# SCH_Left-hand_2023-03-17.net
KiCad netlist of a schematic drawn in EasyEDA
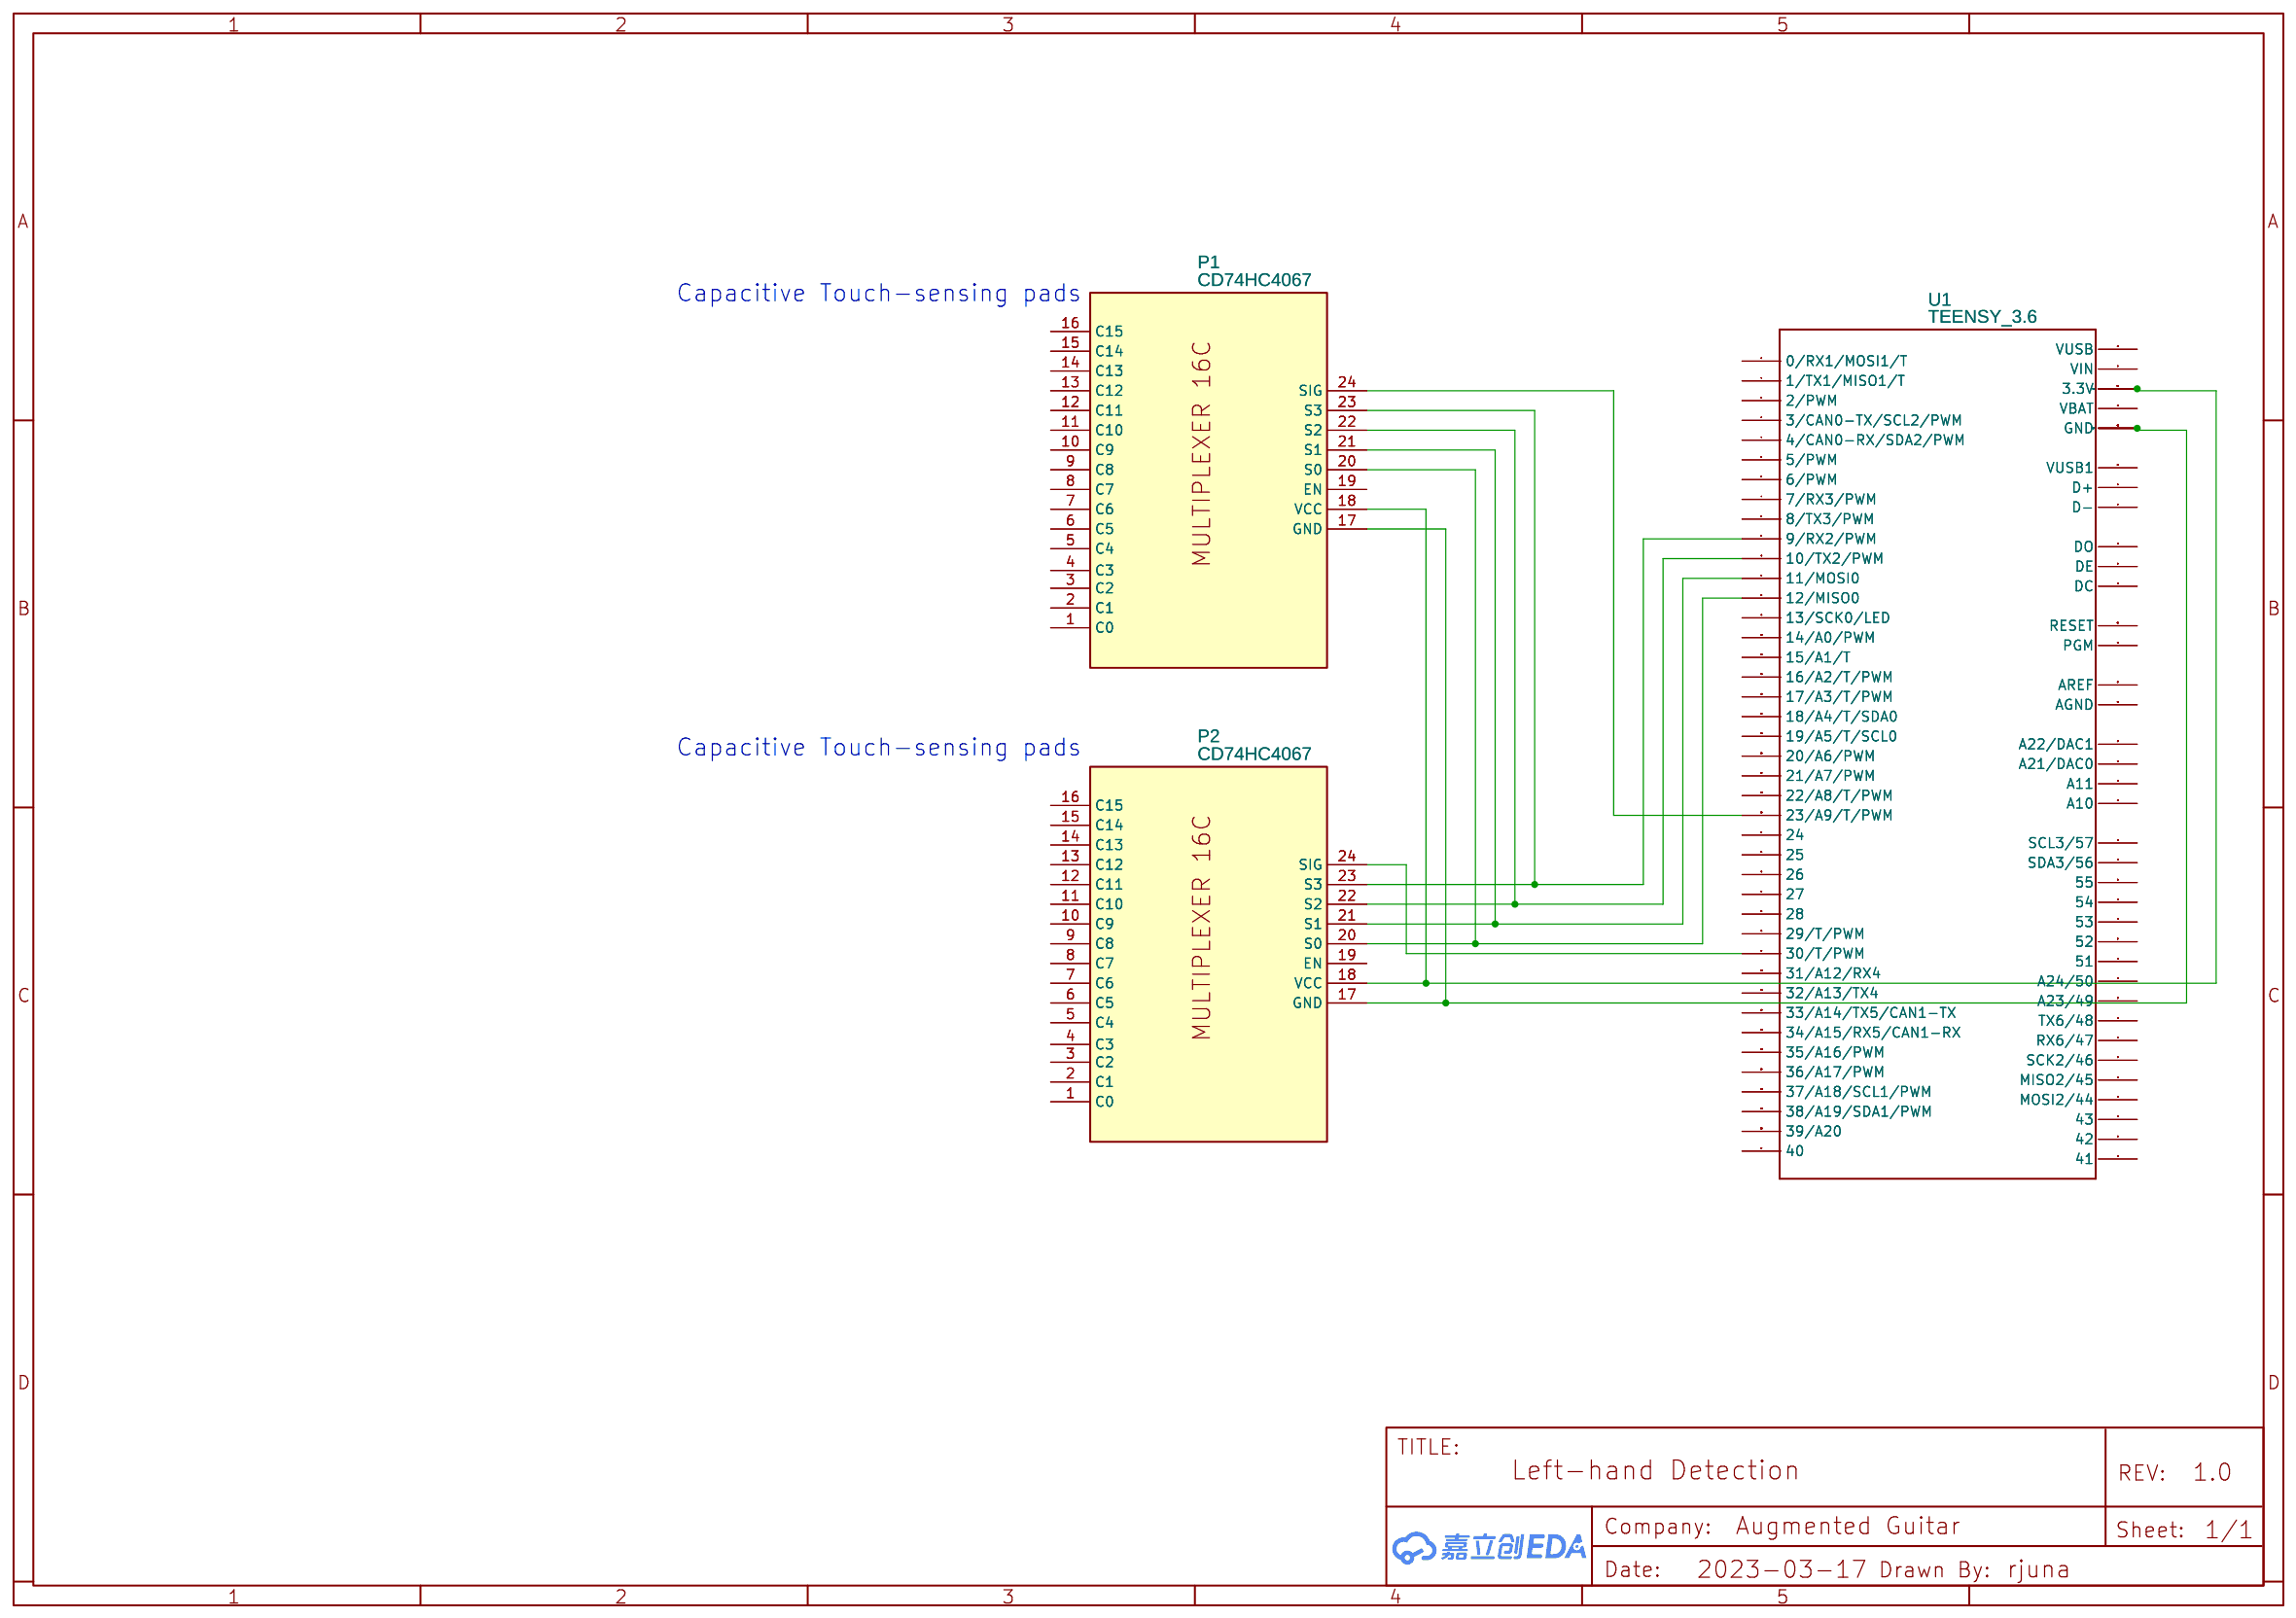
[diagram p0: schematic sheet]

(export (version "E")
  (design (tool "Eeschema 10.0.6"))
  (components
    (comp (ref "P1") (value "CD74HC4067") (libsource (lib "") (part "CD74HC4067")))
    (comp (ref "P2") (value "CD74HC4067") (libsource (lib "") (part "CD74HC4067")))
    (comp (ref "U1") (value "TEENSY_3.6") (libsource (lib "") (part "TEENSY_3.6")))
  )
  (nets
    (net (code "1") (name "Net-(P1-GND)") (class "Default")
      (node (ref "P1") (pin "17") (pinfunction "GND_17") (pintype "unspecified"))
      (node (ref "P2") (pin "17") (pinfunction "GND_17") (pintype "unspecified"))
      (node (ref "U1") (pin "GND") (pinfunction "GND_GND") (pintype "bidirectional"))
      (node (ref "U1") (pin "GND1") (pinfunction "GND_GND1") (pintype "bidirectional"))
      (node (ref "U1") (pin "GND2") (pinfunction "GND_GND2") (pintype "bidirectional"))
      (node (ref "U1") (pin "GND3") (pinfunction "GND_GND3") (pintype "bidirectional"))
      (node (ref "U1") (pin "GND4") (pinfunction "GND_GND4") (pintype "bidirectional"))
      (node (ref "U1") (pin "GND5") (pinfunction "GND_GND5") (pintype "bidirectional"))
      (node (ref "U1") (pin "GND6") (pinfunction "GND_GND6") (pintype "bidirectional"))
    )
    (net (code "2") (name "Net-(P1-S0)") (class "Default")
      (node (ref "P1") (pin "20") (pinfunction "S0_20") (pintype "unspecified"))
      (node (ref "P2") (pin "20") (pinfunction "S0_20") (pintype "unspecified"))
      (node (ref "U1") (pin "12") (pinfunction "12/MISO0_12") (pintype "bidirectional"))
    )
    (net (code "3") (name "Net-(P1-S1)") (class "Default")
      (node (ref "P1") (pin "21") (pinfunction "S1_21") (pintype "unspecified"))
      (node (ref "P2") (pin "21") (pinfunction "S1_21") (pintype "unspecified"))
      (node (ref "U1") (pin "11") (pinfunction "11/MOSI0_11") (pintype "bidirectional"))
    )
    (net (code "4") (name "Net-(P1-S2)") (class "Default")
      (node (ref "P1") (pin "22") (pinfunction "S2_22") (pintype "unspecified"))
      (node (ref "P2") (pin "22") (pinfunction "S2_22") (pintype "unspecified"))
      (node (ref "U1") (pin "10") (pinfunction "10/TX2/PWM_10") (pintype "bidirectional"))
    )
    (net (code "5") (name "Net-(P1-S3)") (class "Default")
      (node (ref "P1") (pin "23") (pinfunction "S3_23") (pintype "unspecified"))
      (node (ref "P2") (pin "23") (pinfunction "S3_23") (pintype "unspecified"))
      (node (ref "U1") (pin "9") (pinfunction "9/RX2/PWM_9") (pintype "bidirectional"))
    )
    (net (code "6") (name "Net-(P1-SIG)") (class "Default")
      (node (ref "P1") (pin "24") (pinfunction "SIG_24") (pintype "unspecified"))
      (node (ref "U1") (pin "23/A9") (pinfunction "23/A9/T/PWM_23/A9") (pintype "bidirectional"))
    )
    (net (code "7") (name "Net-(P1-VCC)") (class "Default")
      (node (ref "P1") (pin "18") (pinfunction "VCC_18") (pintype "unspecified"))
      (node (ref "P2") (pin "18") (pinfunction "VCC_18") (pintype "unspecified"))
      (node (ref "U1") (pin "3.3V") (pinfunction "3.3V_3.3V") (pintype "bidirectional"))
      (node (ref "U1") (pin "3.3V2") (pinfunction "3.3V_3.3V2") (pintype "bidirectional"))
      (node (ref "U1") (pin "3.3V3") (pinfunction "3.3V_3.3V3") (pintype "bidirectional"))
      (node (ref "U1") (pin "3.3V4") (pinfunction "3.3V_3.3V4") (pintype "bidirectional"))
    )
    (net (code "8") (name "Net-(P2-SIG)") (class "Default")
      (node (ref "P2") (pin "24") (pinfunction "SIG_24") (pintype "unspecified"))
      (node (ref "U1") (pin "30") (pinfunction "30/T/PWM_30") (pintype "bidirectional"))
    )
    (net (code "9") (name "unconnected-(P1-C0-Pad1)") (class "Default")
      (node (ref "P1") (pin "1") (pinfunction "C0_1") (pintype "unspecified"))
    )
    (net (code "10") (name "unconnected-(P1-C1-Pad2)") (class "Default")
      (node (ref "P1") (pin "2") (pinfunction "C1_2") (pintype "unspecified"))
    )
    (net (code "11") (name "unconnected-(P1-C2-Pad3)") (class "Default")
      (node (ref "P1") (pin "3") (pinfunction "C2_3") (pintype "unspecified"))
    )
    (net (code "12") (name "unconnected-(P1-C3-Pad4)") (class "Default")
      (node (ref "P1") (pin "4") (pinfunction "C3_4") (pintype "unspecified"))
    )
    (net (code "13") (name "unconnected-(P1-C4-Pad5)") (class "Default")
      (node (ref "P1") (pin "5") (pinfunction "C4_5") (pintype "unspecified"))
    )
    (net (code "14") (name "unconnected-(P1-C5-Pad6)") (class "Default")
      (node (ref "P1") (pin "6") (pinfunction "C5_6") (pintype "unspecified"))
    )
    (net (code "15") (name "unconnected-(P1-C6-Pad7)") (class "Default")
      (node (ref "P1") (pin "7") (pinfunction "C6_7") (pintype "unspecified"))
    )
    (net (code "16") (name "unconnected-(P1-C7-Pad8)") (class "Default")
      (node (ref "P1") (pin "8") (pinfunction "C7_8") (pintype "unspecified"))
    )
    (net (code "17") (name "unconnected-(P1-C8-Pad9)") (class "Default")
      (node (ref "P1") (pin "9") (pinfunction "C8_9") (pintype "unspecified"))
    )
    (net (code "18") (name "unconnected-(P1-C9-Pad10)") (class "Default")
      (node (ref "P1") (pin "10") (pinfunction "C9_10") (pintype "unspecified"))
    )
    (net (code "19") (name "unconnected-(P1-C10-Pad11)") (class "Default")
      (node (ref "P1") (pin "11") (pinfunction "C10_11") (pintype "unspecified"))
    )
    (net (code "20") (name "unconnected-(P1-C11-Pad12)") (class "Default")
      (node (ref "P1") (pin "12") (pinfunction "C11_12") (pintype "unspecified"))
    )
    (net (code "21") (name "unconnected-(P1-C12-Pad13)") (class "Default")
      (node (ref "P1") (pin "13") (pinfunction "C12_13") (pintype "unspecified"))
    )
    (net (code "22") (name "unconnected-(P1-C13-Pad14)") (class "Default")
      (node (ref "P1") (pin "14") (pinfunction "C13_14") (pintype "unspecified"))
    )
    (net (code "23") (name "unconnected-(P1-C14-Pad15)") (class "Default")
      (node (ref "P1") (pin "15") (pinfunction "C14_15") (pintype "unspecified"))
    )
    (net (code "24") (name "unconnected-(P1-C15-Pad16)") (class "Default")
      (node (ref "P1") (pin "16") (pinfunction "C15_16") (pintype "unspecified"))
    )
    (net (code "25") (name "unconnected-(P1-EN-Pad19)") (class "Default")
      (node (ref "P1") (pin "19") (pinfunction "EN_19") (pintype "unspecified"))
    )
    (net (code "26") (name "unconnected-(P2-C0-Pad1)") (class "Default")
      (node (ref "P2") (pin "1") (pinfunction "C0_1") (pintype "unspecified"))
    )
    (net (code "27") (name "unconnected-(P2-C1-Pad2)") (class "Default")
      (node (ref "P2") (pin "2") (pinfunction "C1_2") (pintype "unspecified"))
    )
    (net (code "28") (name "unconnected-(P2-C2-Pad3)") (class "Default")
      (node (ref "P2") (pin "3") (pinfunction "C2_3") (pintype "unspecified"))
    )
    (net (code "29") (name "unconnected-(P2-C3-Pad4)") (class "Default")
      (node (ref "P2") (pin "4") (pinfunction "C3_4") (pintype "unspecified"))
    )
    (net (code "30") (name "unconnected-(P2-C4-Pad5)") (class "Default")
      (node (ref "P2") (pin "5") (pinfunction "C4_5") (pintype "unspecified"))
    )
    (net (code "31") (name "unconnected-(P2-C5-Pad6)") (class "Default")
      (node (ref "P2") (pin "6") (pinfunction "C5_6") (pintype "unspecified"))
    )
    (net (code "32") (name "unconnected-(P2-C6-Pad7)") (class "Default")
      (node (ref "P2") (pin "7") (pinfunction "C6_7") (pintype "unspecified"))
    )
    (net (code "33") (name "unconnected-(P2-C7-Pad8)") (class "Default")
      (node (ref "P2") (pin "8") (pinfunction "C7_8") (pintype "unspecified"))
    )
    (net (code "34") (name "unconnected-(P2-C8-Pad9)") (class "Default")
      (node (ref "P2") (pin "9") (pinfunction "C8_9") (pintype "unspecified"))
    )
    (net (code "35") (name "unconnected-(P2-C9-Pad10)") (class "Default")
      (node (ref "P2") (pin "10") (pinfunction "C9_10") (pintype "unspecified"))
    )
    (net (code "36") (name "unconnected-(P2-C10-Pad11)") (class "Default")
      (node (ref "P2") (pin "11") (pinfunction "C10_11") (pintype "unspecified"))
    )
    (net (code "37") (name "unconnected-(P2-C11-Pad12)") (class "Default")
      (node (ref "P2") (pin "12") (pinfunction "C11_12") (pintype "unspecified"))
    )
    (net (code "38") (name "unconnected-(P2-C12-Pad13)") (class "Default")
      (node (ref "P2") (pin "13") (pinfunction "C12_13") (pintype "unspecified"))
    )
    (net (code "39") (name "unconnected-(P2-C13-Pad14)") (class "Default")
      (node (ref "P2") (pin "14") (pinfunction "C13_14") (pintype "unspecified"))
    )
    (net (code "40") (name "unconnected-(P2-C14-Pad15)") (class "Default")
      (node (ref "P2") (pin "15") (pinfunction "C14_15") (pintype "unspecified"))
    )
    (net (code "41") (name "unconnected-(P2-C15-Pad16)") (class "Default")
      (node (ref "P2") (pin "16") (pinfunction "C15_16") (pintype "unspecified"))
    )
    (net (code "42") (name "unconnected-(P2-EN-Pad19)") (class "Default")
      (node (ref "P2") (pin "19") (pinfunction "EN_19") (pintype "unspecified"))
    )
    (net (code "43") (name "unconnected-(U1-0{slash}RX1{slash}MOSI1{slash}T-Pad0)") (class "Default")
      (node (ref "U1") (pin "0") (pinfunction "0/RX1/MOSI1/T_0") (pintype "bidirectional"))
    )
    (net (code "44") (name "unconnected-(U1-1{slash}TX1{slash}MISO1{slash}T-Pad1)") (class "Default")
      (node (ref "U1") (pin "1") (pinfunction "1/TX1/MISO1/T_1") (pintype "bidirectional"))
    )
    (net (code "45") (name "unconnected-(U1-2{slash}PWM-Pad2)") (class "Default")
      (node (ref "U1") (pin "2") (pinfunction "2/PWM_2") (pintype "bidirectional"))
    )
    (net (code "46") (name "unconnected-(U1-3{slash}CAN0-TX{slash}SCL2{slash}PWM-Pad3)") (class "Default")
      (node (ref "U1") (pin "3") (pinfunction "3/CAN0-TX/SCL2/PWM_3") (pintype "bidirectional"))
    )
    (net (code "47") (name "unconnected-(U1-4{slash}CAN0-RX{slash}SDA2{slash}PWM-Pad4)") (class "Default")
      (node (ref "U1") (pin "4") (pinfunction "4/CAN0-RX/SDA2/PWM_4") (pintype "bidirectional"))
    )
    (net (code "48") (name "unconnected-(U1-5{slash}PWM-Pad5)") (class "Default")
      (node (ref "U1") (pin "5") (pinfunction "5/PWM_5") (pintype "bidirectional"))
    )
    (net (code "49") (name "unconnected-(U1-6{slash}PWM-Pad6)") (class "Default")
      (node (ref "U1") (pin "6") (pinfunction "6/PWM_6") (pintype "bidirectional"))
    )
    (net (code "50") (name "unconnected-(U1-7{slash}RX3{slash}PWM-Pad7)") (class "Default")
      (node (ref "U1") (pin "7") (pinfunction "7/RX3/PWM_7") (pintype "bidirectional"))
    )
    (net (code "51") (name "unconnected-(U1-8{slash}TX3{slash}PWM-Pad8)") (class "Default")
      (node (ref "U1") (pin "8") (pinfunction "8/TX3/PWM_8") (pintype "bidirectional"))
    )
    (net (code "52") (name "unconnected-(U1-13{slash}SCK0{slash}LED-Pad13)") (class "Default")
      (node (ref "U1") (pin "13") (pinfunction "13/SCK0/LED_13") (pintype "bidirectional"))
    )
    (net (code "53") (name "unconnected-(U1-14{slash}A0{slash}PWM-Pad14{slash}A0)") (class "Default")
      (node (ref "U1") (pin "14/A0") (pinfunction "14/A0/PWM_14/A0") (pintype "bidirectional"))
    )
    (net (code "54") (name "unconnected-(U1-15{slash}A1{slash}T-Pad15{slash}A1)") (class "Default")
      (node (ref "U1") (pin "15/A1") (pinfunction "15/A1/T_15/A1") (pintype "bidirectional"))
    )
    (net (code "55") (name "unconnected-(U1-16{slash}A2{slash}T{slash}PWM-Pad16{slash}A2)") (class "Default")
      (node (ref "U1") (pin "16/A2") (pinfunction "16/A2/T/PWM_16/A2") (pintype "bidirectional"))
    )
    (net (code "56") (name "unconnected-(U1-17{slash}A3{slash}T{slash}PWM-Pad17{slash}A3)") (class "Default")
      (node (ref "U1") (pin "17/A3") (pinfunction "17/A3/T/PWM_17/A3") (pintype "bidirectional"))
    )
    (net (code "57") (name "unconnected-(U1-18{slash}A4{slash}T{slash}SDA0-Pad18{slash}A4)") (class "Default")
      (node (ref "U1") (pin "18/A4") (pinfunction "18/A4/T/SDA0_18/A4") (pintype "bidirectional"))
    )
    (net (code "58") (name "unconnected-(U1-19{slash}A5{slash}T{slash}SCL0-Pad19{slash}A5)") (class "Default")
      (node (ref "U1") (pin "19/A5") (pinfunction "19/A5/T/SCL0_19/A5") (pintype "bidirectional"))
    )
    (net (code "59") (name "unconnected-(U1-20{slash}A6{slash}PWM-Pad20{slash}A6)") (class "Default")
      (node (ref "U1") (pin "20/A6") (pinfunction "20/A6/PWM_20/A6") (pintype "bidirectional"))
    )
    (net (code "60") (name "unconnected-(U1-21{slash}A7{slash}PWM-Pad21{slash}A7)") (class "Default")
      (node (ref "U1") (pin "21/A7") (pinfunction "21/A7/PWM_21/A7") (pintype "bidirectional"))
    )
    (net (code "61") (name "unconnected-(U1-22{slash}A8{slash}T{slash}PWM-Pad22{slash}A8)") (class "Default")
      (node (ref "U1") (pin "22/A8") (pinfunction "22/A8/T/PWM_22/A8") (pintype "bidirectional"))
    )
    (net (code "62") (name "unconnected-(U1-29{slash}T{slash}PWM-Pad29)") (class "Default")
      (node (ref "U1") (pin "29") (pinfunction "29/T/PWM_29") (pintype "bidirectional"))
    )
    (net (code "63") (name "unconnected-(U1-31{slash}A12{slash}RX4-Pad31{slash}A12)") (class "Default")
      (node (ref "U1") (pin "31/A12") (pinfunction "31/A12/RX4_31/A12") (pintype "bidirectional"))
    )
    (net (code "64") (name "unconnected-(U1-32{slash}A13{slash}TX4-Pad32{slash}A13)") (class "Default")
      (node (ref "U1") (pin "32/A13") (pinfunction "32/A13/TX4_32/A13") (pintype "bidirectional"))
    )
    (net (code "65") (name "unconnected-(U1-33{slash}A14{slash}TX5{slash}CAN1-TX-Pad33{slash}A14)") (class "Default")
      (node (ref "U1") (pin "33/A14") (pinfunction "33/A14/TX5/CAN1-TX_33/A14") (pintype "bidirectional"))
    )
    (net (code "66") (name "unconnected-(U1-34{slash}A15{slash}RX5{slash}CAN1-RX-Pad34{slash}A15)") (class "Default")
      (node (ref "U1") (pin "34/A15") (pinfunction "34/A15/RX5/CAN1-RX_34/A15") (pintype "bidirectional"))
    )
    (net (code "67") (name "unconnected-(U1-35{slash}A16{slash}PWM-Pad35{slash}A16)") (class "Default")
      (node (ref "U1") (pin "35/A16") (pinfunction "35/A16/PWM_35/A16") (pintype "bidirectional"))
    )
    (net (code "68") (name "unconnected-(U1-36{slash}A17{slash}PWM-Pad36{slash}A17)") (class "Default")
      (node (ref "U1") (pin "36/A17") (pinfunction "36/A17/PWM_36/A17") (pintype "bidirectional"))
    )
    (net (code "69") (name "unconnected-(U1-37{slash}A18{slash}SCL1{slash}PWM-Pad37{slash}A18)") (class "Default")
      (node (ref "U1") (pin "37/A18") (pinfunction "37/A18/SCL1/PWM_37/A18") (pintype "bidirectional"))
    )
    (net (code "70") (name "unconnected-(U1-38{slash}A19{slash}SDA1{slash}PWM-Pad38{slash}A19)") (class "Default")
      (node (ref "U1") (pin "38/A19") (pinfunction "38/A19/SDA1/PWM_38/A19") (pintype "bidirectional"))
    )
    (net (code "71") (name "unconnected-(U1-A21{slash}DAC0-PadA21)") (class "Default")
      (node (ref "U1") (pin "A21") (pinfunction "A21/DAC0_A21") (pintype "bidirectional"))
    )
    (net (code "72") (name "unconnected-(U1-A22{slash}DAC1-PadA22)") (class "Default")
      (node (ref "U1") (pin "A22") (pinfunction "A22/DAC1_A22") (pintype "bidirectional"))
    )
    (net (code "73") (name "unconnected-(U1-A23{slash}49-Pad49)") (class "Default")
      (node (ref "U1") (pin "49") (pinfunction "A23/49_49") (pintype "bidirectional"))
    )
    (net (code "74") (name "unconnected-(U1-A24{slash}50-Pad50)") (class "Default")
      (node (ref "U1") (pin "50") (pinfunction "A24/50_50") (pintype "bidirectional"))
    )
    (net (code "75") (name "unconnected-(U1-MISO2{slash}45-Pad45)") (class "Default")
      (node (ref "U1") (pin "45") (pinfunction "MISO2/45_45") (pintype "bidirectional"))
    )
    (net (code "76") (name "unconnected-(U1-MOSI2{slash}44-Pad44)") (class "Default")
      (node (ref "U1") (pin "44") (pinfunction "MOSI2/44_44") (pintype "bidirectional"))
    )
    (net (code "77") (name "unconnected-(U1-Pad24)") (class "Default")
      (node (ref "U1") (pin "24") (pinfunction "24_24") (pintype "bidirectional"))
    )
    (net (code "78") (name "unconnected-(U1-Pad25)") (class "Default")
      (node (ref "U1") (pin "25") (pinfunction "25_25") (pintype "bidirectional"))
    )
    (net (code "79") (name "unconnected-(U1-Pad26)") (class "Default")
      (node (ref "U1") (pin "26") (pinfunction "26_26") (pintype "bidirectional"))
    )
    (net (code "80") (name "unconnected-(U1-Pad27)") (class "Default")
      (node (ref "U1") (pin "27") (pinfunction "27_27") (pintype "bidirectional"))
    )
    (net (code "81") (name "unconnected-(U1-Pad28)") (class "Default")
      (node (ref "U1") (pin "28") (pinfunction "28_28") (pintype "bidirectional"))
    )
    (net (code "82") (name "unconnected-(U1-Pad39{slash}A20)") (class "Default")
      (node (ref "U1") (pin "39/A20") (pinfunction "39/A20_39/A20") (pintype "bidirectional"))
    )
    (net (code "83") (name "unconnected-(U1-Pad40)") (class "Default")
      (node (ref "U1") (pin "40") (pinfunction "40_40") (pintype "bidirectional"))
    )
    (net (code "84") (name "unconnected-(U1-Pad41)") (class "Default")
      (node (ref "U1") (pin "41") (pinfunction "41_41") (pintype "bidirectional"))
    )
    (net (code "85") (name "unconnected-(U1-Pad42)") (class "Default")
      (node (ref "U1") (pin "42") (pinfunction "42_42") (pintype "bidirectional"))
    )
    (net (code "86") (name "unconnected-(U1-Pad43)") (class "Default")
      (node (ref "U1") (pin "43") (pinfunction "43_43") (pintype "bidirectional"))
    )
    (net (code "87") (name "unconnected-(U1-Pad51)") (class "Default")
      (node (ref "U1") (pin "51") (pinfunction "51_51") (pintype "bidirectional"))
    )
    (net (code "88") (name "unconnected-(U1-Pad52)") (class "Default")
      (node (ref "U1") (pin "52") (pinfunction "52_52") (pintype "bidirectional"))
    )
    (net (code "89") (name "unconnected-(U1-Pad53)") (class "Default")
      (node (ref "U1") (pin "53") (pinfunction "53_53") (pintype "bidirectional"))
    )
    (net (code "90") (name "unconnected-(U1-Pad54)") (class "Default")
      (node (ref "U1") (pin "54") (pinfunction "54_54") (pintype "bidirectional"))
    )
    (net (code "91") (name "unconnected-(U1-Pad55)") (class "Default")
      (node (ref "U1") (pin "55") (pinfunction "55_55") (pintype "bidirectional"))
    )
    (net (code "92") (name "unconnected-(U1-PadA10)") (class "Default")
      (node (ref "U1") (pin "A10") (pinfunction "A10_A10") (pintype "bidirectional"))
    )
    (net (code "93") (name "unconnected-(U1-PadA11)") (class "Default")
      (node (ref "U1") (pin "A11") (pinfunction "A11_A11") (pintype "bidirectional"))
    )
    (net (code "94") (name "unconnected-(U1-PadAGND)") (class "Default")
      (node (ref "U1") (pin "AGND") (pinfunction "AGND_AGND") (pintype "bidirectional"))
    )
    (net (code "95") (name "unconnected-(U1-PadAREF)") (class "Default")
      (node (ref "U1") (pin "AREF") (pinfunction "AREF_AREF") (pintype "bidirectional"))
    )
    (net (code "96") (name "unconnected-(U1-PadD+)") (class "Default")
      (node (ref "U1") (pin "D+") (pinfunction "D+_D+") (pintype "bidirectional"))
    )
    (net (code "97") (name "unconnected-(U1-PadD-)") (class "Default")
      (node (ref "U1") (pin "D-") (pinfunction "D-_D-") (pintype "bidirectional"))
    )
    (net (code "98") (name "unconnected-(U1-PadDC)") (class "Default")
      (node (ref "U1") (pin "DC") (pinfunction "DC_DC") (pintype "bidirectional"))
    )
    (net (code "99") (name "unconnected-(U1-PadDE)") (class "Default")
      (node (ref "U1") (pin "DE") (pinfunction "DE_DE") (pintype "bidirectional"))
    )
    (net (code "100") (name "unconnected-(U1-PadDO)") (class "Default")
      (node (ref "U1") (pin "DO") (pinfunction "DO_DO") (pintype "bidirectional"))
    )
    (net (code "101") (name "unconnected-(U1-PadPGM)") (class "Default")
      (node (ref "U1") (pin "PGM") (pinfunction "PGM_PGM") (pintype "bidirectional"))
    )
    (net (code "102") (name "unconnected-(U1-PadRESET)") (class "Default")
      (node (ref "U1") (pin "RESET") (pinfunction "RESET_RESET") (pintype "bidirectional"))
    )
    (net (code "103") (name "unconnected-(U1-PadVBAT)") (class "Default")
      (node (ref "U1") (pin "VBAT") (pinfunction "VBAT_VBAT") (pintype "bidirectional"))
    )
    (net (code "104") (name "unconnected-(U1-PadVIN)") (class "Default")
      (node (ref "U1") (pin "VIN") (pinfunction "VIN_VIN") (pintype "bidirectional"))
    )
    (net (code "105") (name "unconnected-(U1-PadVUSB)") (class "Default")
      (node (ref "U1") (pin "VUSB") (pinfunction "VUSB_VUSB") (pintype "bidirectional"))
    )
    (net (code "106") (name "unconnected-(U1-PadVUSB1)") (class "Default")
      (node (ref "U1") (pin "VUSB1") (pinfunction "VUSB1_VUSB1") (pintype "bidirectional"))
    )
    (net (code "107") (name "unconnected-(U1-RX6{slash}47-Pad47)") (class "Default")
      (node (ref "U1") (pin "47") (pinfunction "RX6/47_47") (pintype "bidirectional"))
    )
    (net (code "108") (name "unconnected-(U1-SCK2{slash}46-Pad46)") (class "Default")
      (node (ref "U1") (pin "46") (pinfunction "SCK2/46_46") (pintype "bidirectional"))
    )
    (net (code "109") (name "unconnected-(U1-SCL3{slash}57-Pad57)") (class "Default")
      (node (ref "U1") (pin "57") (pinfunction "SCL3/57_57") (pintype "bidirectional"))
    )
    (net (code "110") (name "unconnected-(U1-SDA3{slash}56-Pad56)") (class "Default")
      (node (ref "U1") (pin "56") (pinfunction "SDA3/56_56") (pintype "bidirectional"))
    )
    (net (code "111") (name "unconnected-(U1-TX6{slash}48-Pad48)") (class "Default")
      (node (ref "U1") (pin "48") (pinfunction "TX6/48_48") (pintype "bidirectional"))
    )
  )
)
